# Power_Supply.net
KiCad netlist of a schematic drawn in Altium Designer
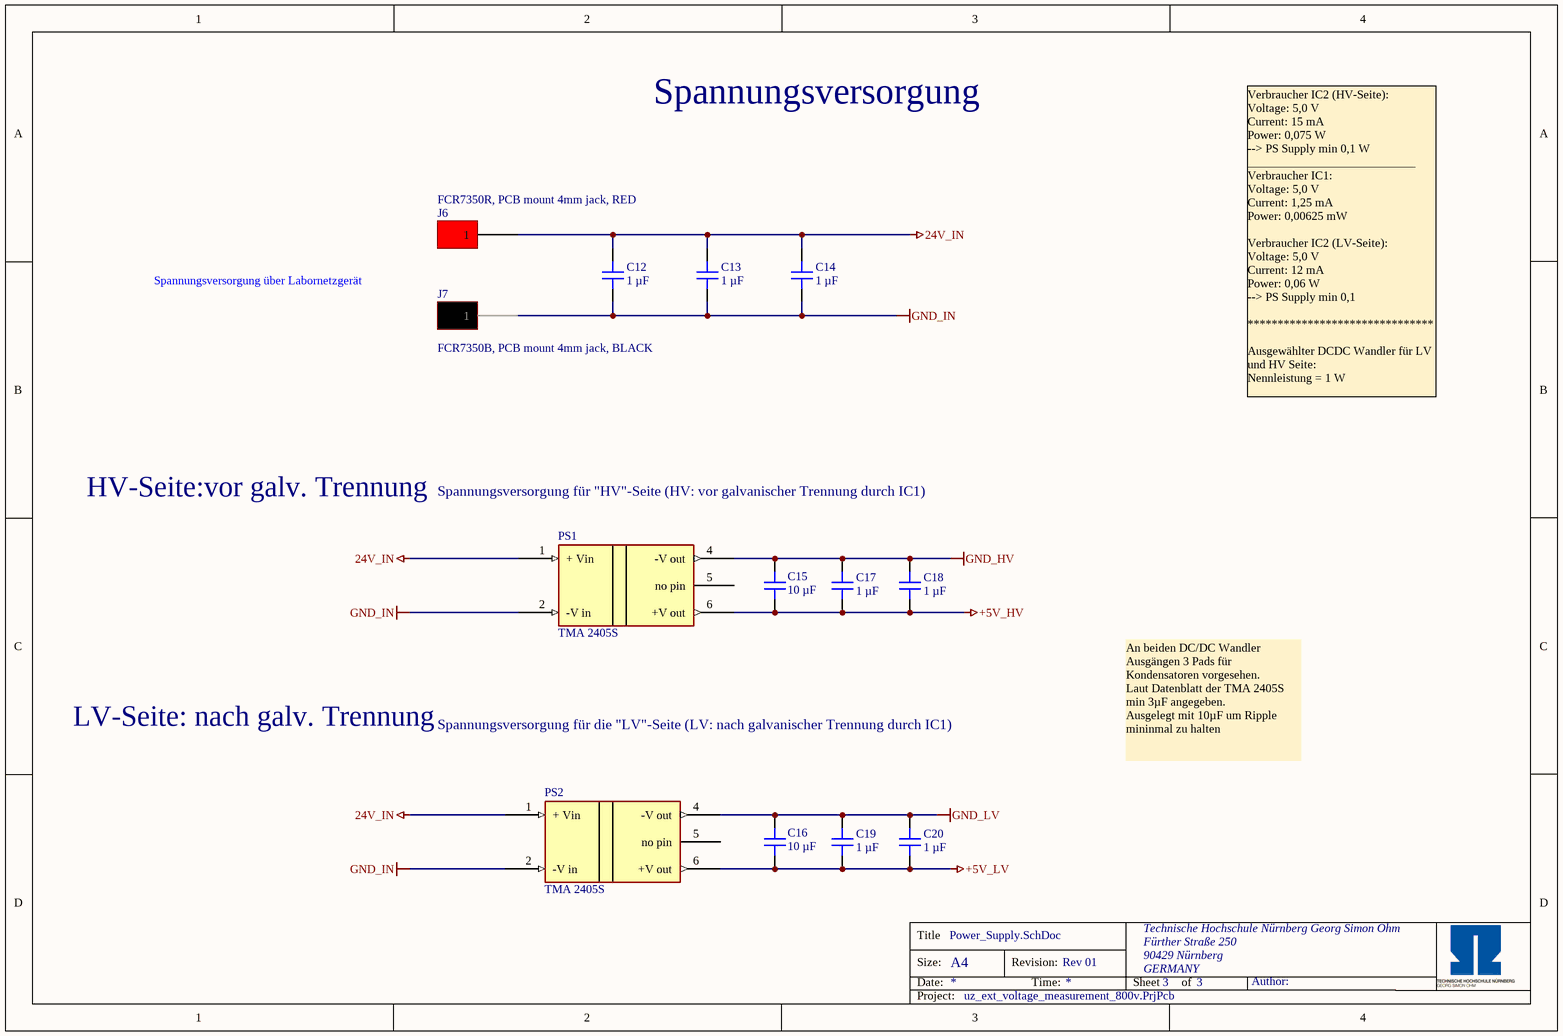
[diagram p0: Power_Supply.SchDoc]

(export (version "E")
  (design (tool "Eeschema 10.0.6"))
  (components
    (comp (ref "C12")
      (value "1 µF")
      (footprint "C_0603")
      (description "50V 1uF X5R ±10% 0603  Multilayer Ceramic Capacitors MLCC - SMD/SMT ROHS")
      (fields
        (field (name "MANUFACTURER") "Samsung Electro-Mechanics")
        (field (name "MANUFACTURER PART NUMBER") "CL10A105KB8NNNC")
        (field (name "CREATED FROM") "MGremer")
      )
      (libsource (lib "user") (part "Capacitor"))
    )
    (comp (ref "C13")
      (value "1 µF")
      (footprint "C_0603")
      (description "50V 1uF X5R ±10% 0603  Multilayer Ceramic Capacitors MLCC - SMD/SMT ROHS")
      (fields
        (field (name "MANUFACTURER") "Samsung Electro-Mechanics")
        (field (name "MANUFACTURER PART NUMBER") "CL10A105KB8NNNC")
        (field (name "CREATED FROM") "MGremer")
      )
      (libsource (lib "user") (part "Capacitor"))
    )
    (comp (ref "C14")
      (value "1 µF")
      (footprint "C_0603")
      (description "50V 1uF X5R ±10% 0603  Multilayer Ceramic Capacitors MLCC - SMD/SMT ROHS")
      (fields
        (field (name "MANUFACTURER") "Samsung Electro-Mechanics")
        (field (name "MANUFACTURER PART NUMBER") "CL10A105KB8NNNC")
        (field (name "CREATED FROM") "MGremer")
      )
      (libsource (lib "user") (part "Capacitor"))
    )
    (comp (ref "C15")
      (value "10 µF")
      (footprint "C_0603")
      (description "Capacitor 0603, 16 VDC, 10 µF, X5R")
      (fields
        (field (name "MANUFACTURER PART NUMBER") "CL10A106MO8NQNC")
        (field (name "MANUFACTURER") "Samsung Electro-Mechanics")
        (field (name "CREATED FROM") "AGeiger")
      )
      (libsource (lib "user") (part "Capacitor"))
    )
    (comp (ref "C16")
      (value "10 µF")
      (footprint "C_0603")
      (description "Capacitor 0603, 16 VDC, 10 µF, X5R")
      (fields
        (field (name "MANUFACTURER PART NUMBER") "CL10A106MO8NQNC")
        (field (name "MANUFACTURER") "Samsung Electro-Mechanics")
        (field (name "CREATED FROM") "AGeiger")
      )
      (libsource (lib "user") (part "Capacitor"))
    )
    (comp (ref "C17")
      (value "1 µF")
      (footprint "C_0603")
      (description "50V 1uF X5R ±10% 0603  Multilayer Ceramic Capacitors MLCC - SMD/SMT ROHS")
      (fields
        (field (name "MANUFACTURER") "Samsung Electro-Mechanics")
        (field (name "MANUFACTURER PART NUMBER") "CL10A105KB8NNNC")
        (field (name "CREATED FROM") "MGremer")
      )
      (libsource (lib "user") (part "Capacitor"))
    )
    (comp (ref "C18")
      (value "1 µF")
      (footprint "C_0603")
      (description "50V 1uF X5R ±10% 0603  Multilayer Ceramic Capacitors MLCC - SMD/SMT ROHS")
      (fields
        (field (name "MANUFACTURER") "Samsung Electro-Mechanics")
        (field (name "MANUFACTURER PART NUMBER") "CL10A105KB8NNNC")
        (field (name "CREATED FROM") "MGremer")
      )
      (libsource (lib "user") (part "Capacitor"))
    )
    (comp (ref "C19")
      (value "1 µF")
      (footprint "C_0603")
      (description "50V 1uF X5R ±10% 0603  Multilayer Ceramic Capacitors MLCC - SMD/SMT ROHS")
      (fields
        (field (name "MANUFACTURER") "Samsung Electro-Mechanics")
        (field (name "MANUFACTURER PART NUMBER") "CL10A105KB8NNNC")
        (field (name "CREATED FROM") "MGremer")
      )
      (libsource (lib "user") (part "Capacitor"))
    )
    (comp (ref "C20")
      (value "1 µF")
      (footprint "C_0603")
      (description "50V 1uF X5R ±10% 0603  Multilayer Ceramic Capacitors MLCC - SMD/SMT ROHS")
      (fields
        (field (name "MANUFACTURER") "Samsung Electro-Mechanics")
        (field (name "MANUFACTURER PART NUMBER") "CL10A105KB8NNNC")
        (field (name "CREATED FROM") "MGremer")
      )
      (libsource (lib "user") (part "Capacitor"))
    )
    (comp (ref "J6")
      (value "FCR7350R, PCB mount 4mm jack, RED")
      (footprint "FCR7350")
      (description "FCR7350B, 1000V, 24A, RED")
      (fields
        (field (name "MANUFACTURER PART NUMBER") "FCR7350R")
        (field (name "MANUFACTURER") "Cliff")
        (field (name "CREATED FROM") "DHufnagel")
      )
      (libsource (lib "user") (part "FCR7350R"))
    )
    (comp (ref "J7")
      (value "FCR7350B, PCB mount 4mm jack, BLACK")
      (footprint "FCR7350")
      (description "FCR7350B, 1000V, 24A, BLACK")
      (fields
        (field (name "MANUFACTURER PART NUMBER") "FCR7350B")
        (field (name "MANUFACTURER") "Cliff")
        (field (name "CREATED FROM") "DHufnagel")
      )
      (libsource (lib "user") (part "FCR7350B"))
    )
    (comp (ref "PS1")
      (value "TMA 2405S")
      (footprint "eigene_lib_alt:TMA 2405D")
      (libsource (lib "eigene_lib_alt") (part "TMA 2405S"))
    )
    (comp (ref "PS2")
      (value "TMA 2405S")
      (footprint "eigene_lib_alt:TMA 2405D")
      (libsource (lib "eigene_lib_alt") (part "TMA 2405S"))
    )
  )
  (nets
    (net (code "1") (name "+5V_HV") (class "Default")
      (node (ref "C15") (pin "1") (pinfunction "1_1") (pintype "passive"))
      (node (ref "C17") (pin "1") (pinfunction "1_1") (pintype "passive"))
      (node (ref "C18") (pin "1") (pinfunction "1_1") (pintype "passive"))
      (node (ref "PS1") (pin "6") (pinfunction "+V_out_6") (pintype "output"))
    )
    (net (code "2") (name "+5V_LV") (class "Default")
      (node (ref "C16") (pin "1") (pinfunction "1_1") (pintype "passive"))
      (node (ref "C19") (pin "1") (pinfunction "1_1") (pintype "passive"))
      (node (ref "C20") (pin "1") (pinfunction "1_1") (pintype "passive"))
      (node (ref "PS2") (pin "6") (pinfunction "+V_out_6") (pintype "output"))
    )
    (net (code "3") (name "24V_IN") (class "Default")
      (node (ref "C12") (pin "1") (pinfunction "1_1") (pintype "passive"))
      (node (ref "C13") (pin "1") (pinfunction "1_1") (pintype "passive"))
      (node (ref "C14") (pin "1") (pinfunction "1_1") (pintype "passive"))
      (node (ref "J6") (pin "1") (pinfunction "1_1") (pintype "passive"))
      (node (ref "PS1") (pin "1") (pinfunction "+_Vin_1") (pintype "input"))
      (node (ref "PS2") (pin "1") (pinfunction "+_Vin_1") (pintype "input"))
    )
    (net (code "4") (name "GND_HV") (class "Default")
      (node (ref "C15") (pin "2") (pinfunction "2_2") (pintype "passive"))
      (node (ref "C17") (pin "2") (pinfunction "2_2") (pintype "passive"))
      (node (ref "C18") (pin "2") (pinfunction "2_2") (pintype "passive"))
      (node (ref "PS1") (pin "4") (pinfunction "-V_out_4") (pintype "output"))
    )
    (net (code "5") (name "GND_IN") (class "Default")
      (node (ref "C12") (pin "2") (pinfunction "2_2") (pintype "passive"))
      (node (ref "C13") (pin "2") (pinfunction "2_2") (pintype "passive"))
      (node (ref "C14") (pin "2") (pinfunction "2_2") (pintype "passive"))
      (node (ref "J7") (pin "1") (pinfunction "1_1") (pintype "passive"))
      (node (ref "PS1") (pin "2") (pinfunction "-V_in_2") (pintype "input"))
      (node (ref "PS2") (pin "2") (pinfunction "-V_in_2") (pintype "input"))
    )
    (net (code "6") (name "GND_LV") (class "Default")
      (node (ref "C16") (pin "2") (pinfunction "2_2") (pintype "passive"))
      (node (ref "C19") (pin "2") (pinfunction "2_2") (pintype "passive"))
      (node (ref "C20") (pin "2") (pinfunction "2_2") (pintype "passive"))
      (node (ref "PS2") (pin "4") (pinfunction "-V_out_4") (pintype "output"))
    )
    (net (code "7") (name "unconnected-(PS1-no_pin-Pad5)") (class "Default")
      (node (ref "PS1") (pin "5") (pinfunction "no_pin_5") (pintype "passive"))
    )
    (net (code "8") (name "unconnected-(PS2-no_pin-Pad5)") (class "Default")
      (node (ref "PS2") (pin "5") (pinfunction "no_pin_5") (pintype "passive"))
    )
  )
)
